# Spring2020.net
KiCad netlist of a schematic drawn in EAGLE
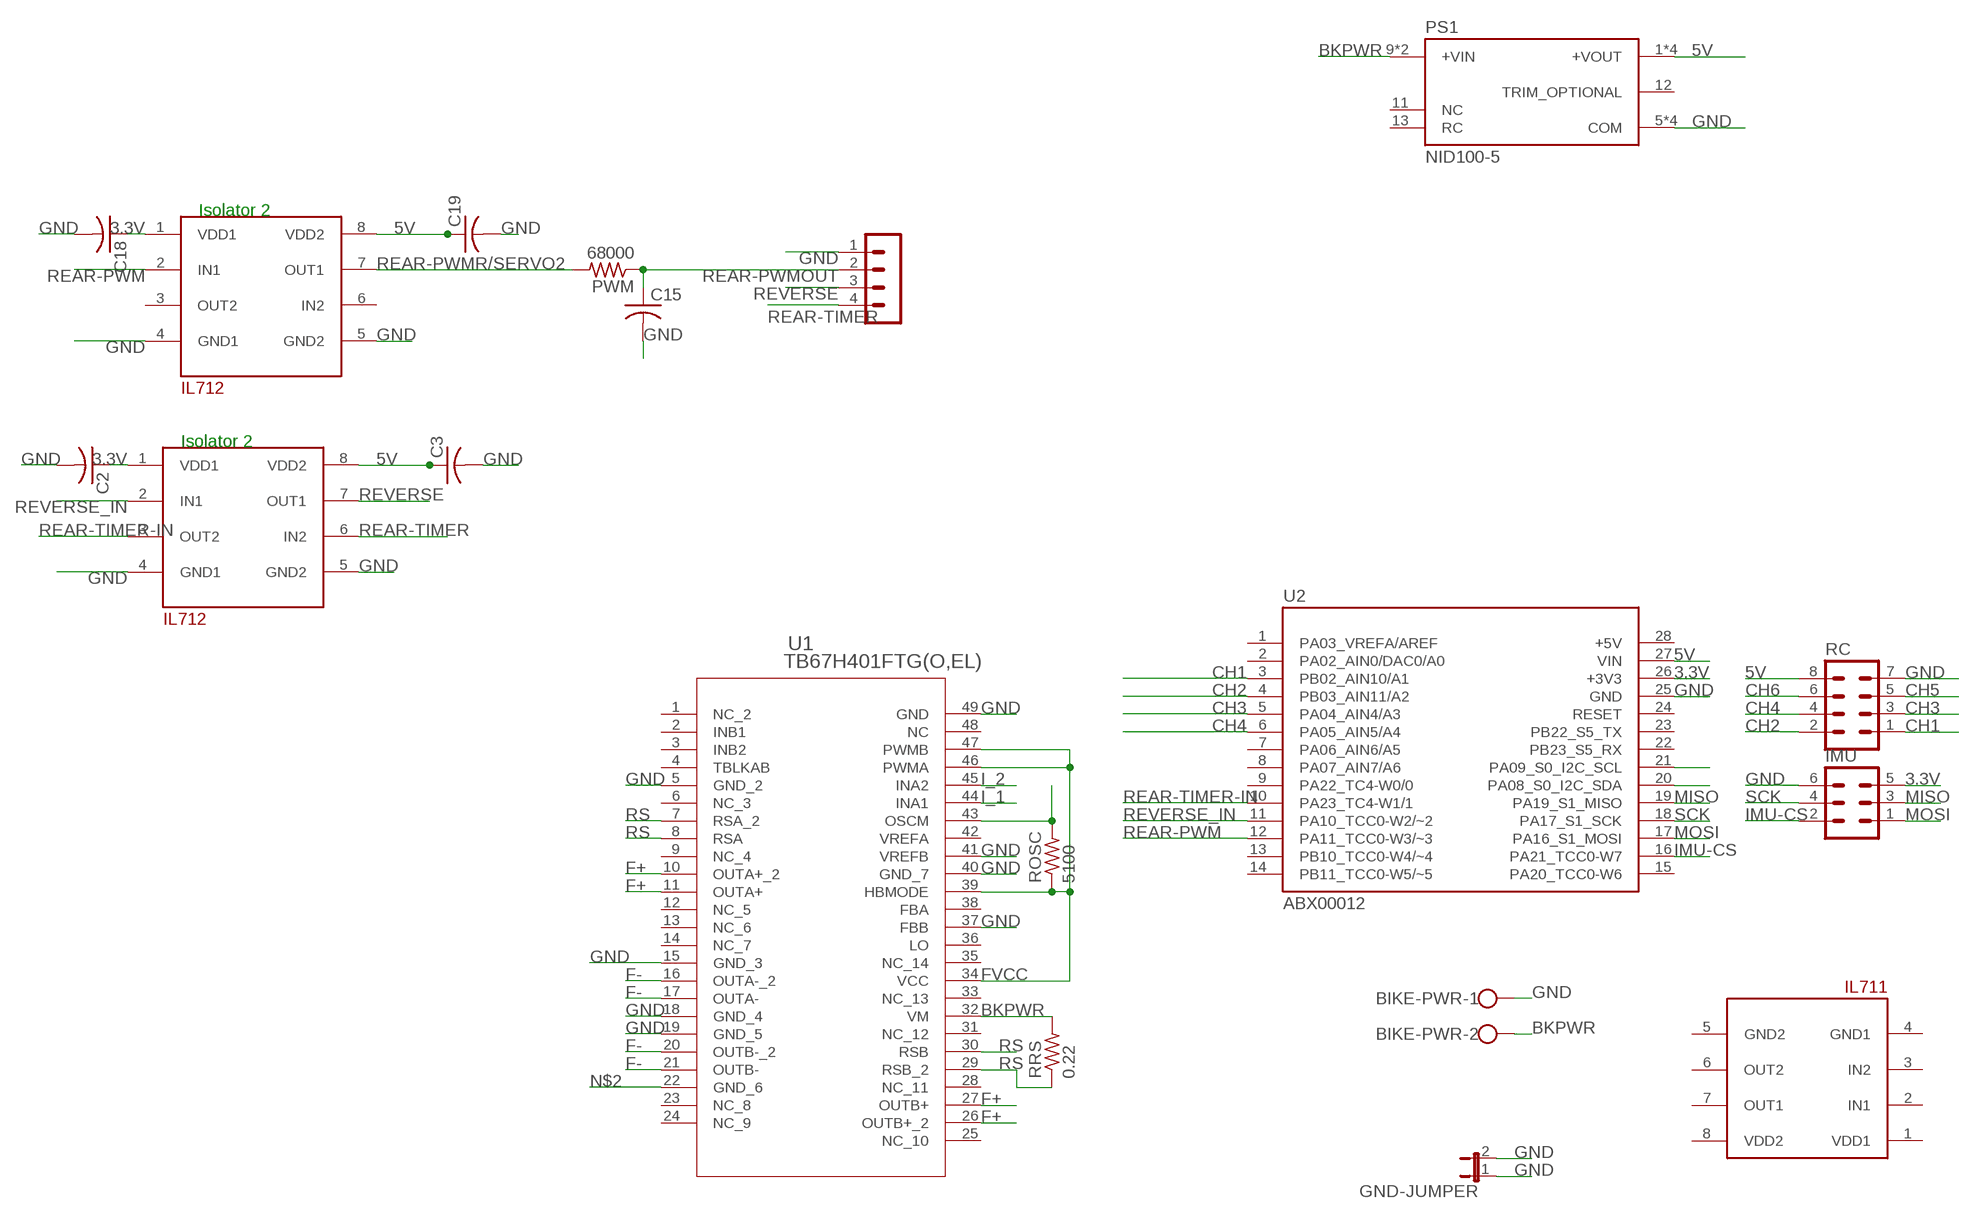
[diagram p0: schematic, sheet 1]

(export (version "E")
  (design (tool "Eeschema 10.0.6"))
  (components
    (comp (ref "BIKE-PWR")
      (value "W237-102")
      (footprint "eagle-import:W237-102")
      (fields (field (name "MPN") "237-102"))
      (libsource (lib "eagle-import") (part "W237-102"))
    )
    (comp (ref "C2")
      (value "C-US025-050X050")
      (footprint "eagle-import:C025-050X050")
      (libsource (lib "eagle-import") (part "C-US025-050X050"))
    )
    (comp (ref "C3")
      (value "C-US025-050X050")
      (footprint "eagle-import:C025-050X050")
      (libsource (lib "eagle-import") (part "C-US025-050X050"))
    )
    (comp (ref "C15")
      (value "C-US025-050X050")
      (footprint "eagle-import:C025-050X050")
      (libsource (lib "eagle-import") (part "C-US025-050X050"))
    )
    (comp (ref "C18")
      (value "C-US025-050X050")
      (footprint "eagle-import:C025-050X050")
      (libsource (lib "eagle-import") (part "C-US025-050X050"))
    )
    (comp (ref "C19")
      (value "C-US025-050X050")
      (footprint "eagle-import:C025-050X050")
      (libsource (lib "eagle-import") (part "C-US025-050X050"))
    )
    (comp (ref "GND-JUMPER")
      (value "JP1E")
      (footprint "eagle-import:JP1")
      (libsource (lib "eagle-import") (part "JP1E"))
    )
    (comp (ref "IMU")
      (value "MA03-2")
      (footprint "eagle-import:MA03-2")
      (libsource (lib "eagle-import") (part "MA03-2"))
    )
    (comp (ref "PS1")
      (value "NID100-5")
      (footprint "eagle-import:CONV_NID100-5")
      (fields (field (name "MANUFACTURER") "Meanwell"))
      (libsource (lib "eagle-import") (part "NID100-5"))
    )
    (comp (ref "PWM")
      (value "68000")
      (footprint "eagle-import:0204V")
      (libsource (lib "eagle-import") (part "R-US_0204/2V"))
    )
    (comp (ref "RC")
      (value "MA04-2")
      (footprint "eagle-import:MA04-2")
      (libsource (lib "eagle-import") (part "MA04-2"))
    )
    (comp (ref "REAR-MOTOR")
      (value "MA04-1")
      (footprint "eagle-import:MA04-1")
      (libsource (lib "eagle-import") (part "MA04-1"))
    )
    (comp (ref "ROSC")
      (value "5100")
      (footprint "eagle-import:0204V")
      (libsource (lib "eagle-import") (part "R-US_0204/2V"))
    )
    (comp (ref "RRS")
      (value "0.22")
      (footprint "eagle-import:0204V")
      (libsource (lib "eagle-import") (part "R-US_0204/2V"))
    )
    (comp (ref "U$2")
      (value "IL-712")
      (footprint "eagle-import:8PINSOIC")
      (libsource (lib "eagle-import") (part "IL-712"))
    )
    (comp (ref "U$3")
      (value "IL-711")
      (footprint "eagle-import:8PINSOIC")
      (libsource (lib "eagle-import") (part "IL-711"))
    )
    (comp (ref "U$7")
      (value "IL-712")
      (footprint "eagle-import:8PINSOIC")
      (libsource (lib "eagle-import") (part "IL-712"))
    )
    (comp (ref "U1")
      (value "TB67H401FTG(O,EL)")
      (footprint "eagle-import:P-VQFN48-0707-0P50-004_TOS")
      (fields (field (name "COPYRIGHT") "Copyright (C) 2022 Ultra Librarian. All rights reserved."))
      (libsource (lib "eagle-import") (part "TB67H401FTG(O,EL)"))
    )
    (comp (ref "U2")
      (value "ABX00012")
      (footprint "eagle-import:ARDUINO_ABX00012")
      (fields (field (name "MANUFACTURER") "Arduino"))
      (libsource (lib "eagle-import") (part "ABX00012"))
    )
  )
  (nets
    (net (code "1") (name "/+5V") (class "Default")
      (node (ref "U2") (pin "28") (pinfunction "+5V_28") (pintype "power_in"))
    )
    (net (code "2") (name "/3.3V") (class "Default")
      (node (ref "C18") (pin "1") (pinfunction "1_1") (pintype "passive"))
      (node (ref "C2") (pin "1") (pinfunction "1_1") (pintype "passive"))
      (node (ref "IMU") (pin "5") (pinfunction "5_5") (pintype "passive"))
      (node (ref "U$2") (pin "1") (pinfunction "VDD1_1") (pintype "power_in"))
      (node (ref "U$7") (pin "1") (pinfunction "VDD1_1") (pintype "power_in"))
      (node (ref "U2") (pin "26") (pinfunction "+3V3_26") (pintype "power_in"))
    )
    (net (code "3") (name "/5V") (class "Default")
      (node (ref "C19") (pin "1") (pinfunction "1_1") (pintype "passive"))
      (node (ref "C3") (pin "1") (pinfunction "1_1") (pintype "passive"))
      (node (ref "PS1") (pin "1") (pinfunction "+VOUT_1") (pintype "output"))
      (node (ref "PS1") (pin "2") (pinfunction "+VOUT_2") (pintype "output"))
      (node (ref "PS1") (pin "3") (pinfunction "+VOUT_3") (pintype "output"))
      (node (ref "PS1") (pin "4") (pinfunction "+VOUT_4") (pintype "output"))
      (node (ref "RC") (pin "8") (pinfunction "8_8") (pintype "passive"))
      (node (ref "U$2") (pin "8") (pinfunction "VDD2_8") (pintype "power_in"))
      (node (ref "U$7") (pin "8") (pinfunction "VDD2_8") (pintype "power_in"))
      (node (ref "U2") (pin "27") (pinfunction "VIN_27") (pintype "power_in"))
    )
    (net (code "4") (name "/BKPWR") (class "Default")
      (node (ref "BIKE-PWR") (pin "2") (pinfunction "KL_2") (pintype "passive"))
      (node (ref "PS1") (pin "10") (pinfunction "+VIN_10") (pintype "input"))
      (node (ref "PS1") (pin "9") (pinfunction "+VIN_9") (pintype "input"))
      (node (ref "RRS") (pin "2") (pinfunction "2_2") (pintype "passive"))
      (node (ref "U1") (pin "32") (pinfunction "VM_32") (pintype "passive"))
    )
    (net (code "5") (name "/CH1") (class "Default")
      (node (ref "RC") (pin "1") (pinfunction "1_1") (pintype "passive"))
      (node (ref "U2") (pin "3") (pinfunction "PB02_AIN10/A1_3") (pintype "bidirectional"))
    )
    (net (code "6") (name "/CH2") (class "Default")
      (node (ref "RC") (pin "2") (pinfunction "2_2") (pintype "passive"))
      (node (ref "U2") (pin "4") (pinfunction "PB03_AIN11/A2_4") (pintype "bidirectional"))
    )
    (net (code "7") (name "/CH3") (class "Default")
      (node (ref "RC") (pin "3") (pinfunction "3_3") (pintype "passive"))
      (node (ref "U2") (pin "5") (pinfunction "PA04_AIN4/A3_5") (pintype "bidirectional"))
    )
    (net (code "8") (name "/CH4") (class "Default")
      (node (ref "RC") (pin "4") (pinfunction "4_4") (pintype "passive"))
      (node (ref "U2") (pin "6") (pinfunction "PA05_AIN5/A4_6") (pintype "bidirectional"))
    )
    (net (code "9") (name "/CH5") (class "Default")
      (node (ref "RC") (pin "5") (pinfunction "5_5") (pintype "passive"))
    )
    (net (code "10") (name "/CH6") (class "Default")
      (node (ref "RC") (pin "6") (pinfunction "6_6") (pintype "passive"))
    )
    (net (code "11") (name "/F+") (class "Default")
      (node (ref "U1") (pin "10") (pinfunction "OUTA+_2_10") (pintype "output"))
      (node (ref "U1") (pin "11") (pinfunction "OUTA+_11") (pintype "output"))
      (node (ref "U1") (pin "26") (pinfunction "OUTB+_2_26") (pintype "output"))
      (node (ref "U1") (pin "27") (pinfunction "OUTB+_27") (pintype "output"))
    )
    (net (code "12") (name "/F-") (class "Default")
      (node (ref "U1") (pin "16") (pinfunction "OUTA-_2_16") (pintype "output"))
      (node (ref "U1") (pin "17") (pinfunction "OUTA-_17") (pintype "output"))
      (node (ref "U1") (pin "20") (pinfunction "OUTB-_2_20") (pintype "output"))
      (node (ref "U1") (pin "21") (pinfunction "OUTB-_21") (pintype "output"))
    )
    (net (code "13") (name "/FVCC") (class "Default")
      (node (ref "ROSC") (pin "1") (pinfunction "1_1") (pintype "passive"))
      (node (ref "U1") (pin "34") (pinfunction "VCC_34") (pintype "power_in"))
      (node (ref "U1") (pin "39") (pinfunction "HBMODE_39") (pintype "passive"))
      (node (ref "U1") (pin "46") (pinfunction "PWMA_46") (pintype "passive"))
      (node (ref "U1") (pin "47") (pinfunction "PWMB_47") (pintype "passive"))
    )
    (net (code "14") (name "/GND") (class "Default")
      (node (ref "BIKE-PWR") (pin "1") (pinfunction "KL_1") (pintype "passive"))
      (node (ref "C15") (pin "2") (pinfunction "2_2") (pintype "passive"))
      (node (ref "C18") (pin "2") (pinfunction "2_2") (pintype "passive"))
      (node (ref "C19") (pin "2") (pinfunction "2_2") (pintype "passive"))
      (node (ref "C2") (pin "2") (pinfunction "2_2") (pintype "passive"))
      (node (ref "C3") (pin "2") (pinfunction "2_2") (pintype "passive"))
      (node (ref "GND-JUMPER") (pin "1") (pinfunction "1_1") (pintype "passive"))
      (node (ref "GND-JUMPER") (pin "2") (pinfunction "2_2") (pintype "passive"))
      (node (ref "IMU") (pin "6") (pinfunction "6_6") (pintype "passive"))
      (node (ref "PS1") (pin "5") (pinfunction "COM_5") (pintype "passive"))
      (node (ref "PS1") (pin "6") (pinfunction "COM_6") (pintype "passive"))
      (node (ref "PS1") (pin "7") (pinfunction "COM_7") (pintype "passive"))
      (node (ref "PS1") (pin "8") (pinfunction "COM_8") (pintype "passive"))
      (node (ref "RC") (pin "7") (pinfunction "7_7") (pintype "passive"))
      (node (ref "REAR-MOTOR") (pin "1") (pinfunction "1_1") (pintype "passive"))
      (node (ref "U$2") (pin "4") (pinfunction "GND1_4") (pintype "power_in"))
      (node (ref "U$2") (pin "5") (pinfunction "GND2_5") (pintype "power_in"))
      (node (ref "U$7") (pin "4") (pinfunction "GND1_4") (pintype "power_in"))
      (node (ref "U$7") (pin "5") (pinfunction "GND2_5") (pintype "power_in"))
      (node (ref "U1") (pin "15") (pinfunction "GND_3_15") (pintype "passive"))
      (node (ref "U1") (pin "18") (pinfunction "GND_4_18") (pintype "passive"))
      (node (ref "U1") (pin "19") (pinfunction "GND_5_19") (pintype "passive"))
      (node (ref "U1") (pin "37") (pinfunction "FBB_37") (pintype "passive"))
      (node (ref "U1") (pin "40") (pinfunction "GND_7_40") (pintype "passive"))
      (node (ref "U1") (pin "41") (pinfunction "VREFB_41") (pintype "power_in"))
      (node (ref "U1") (pin "49") (pinfunction "GND_49") (pintype "passive"))
      (node (ref "U1") (pin "5") (pinfunction "GND_2_5") (pintype "passive"))
      (node (ref "U2") (pin "25") (pinfunction "GND_25") (pintype "power_in"))
    )
    (net (code "15") (name "/GND1") (class "Default")
      (node (ref "U$3") (pin "4") (pinfunction "GND1_4") (pintype "power_in"))
    )
    (net (code "16") (name "/GND2") (class "Default")
      (node (ref "U$3") (pin "5") (pinfunction "GND2_5") (pintype "power_in"))
    )
    (net (code "17") (name "/IMU-CS") (class "Default")
      (node (ref "IMU") (pin "2") (pinfunction "2_2") (pintype "passive"))
      (node (ref "U2") (pin "16") (pinfunction "PA21_TCC0-W7_16") (pintype "bidirectional"))
    )
    (net (code "18") (name "/I_1") (class "Default")
      (node (ref "U1") (pin "44") (pinfunction "INA1_44") (pintype "input"))
    )
    (net (code "19") (name "/I_2") (class "Default")
      (node (ref "U1") (pin "45") (pinfunction "INA2_45") (pintype "input"))
    )
    (net (code "20") (name "/MISO") (class "Default")
      (node (ref "IMU") (pin "3") (pinfunction "3_3") (pintype "passive"))
      (node (ref "U2") (pin "19") (pinfunction "PA19_S1_MISO_19") (pintype "bidirectional"))
    )
    (net (code "21") (name "/MOSI") (class "Default")
      (node (ref "IMU") (pin "1") (pinfunction "1_1") (pintype "passive"))
      (node (ref "U2") (pin "17") (pinfunction "PA16_S1_MOSI_17") (pintype "bidirectional"))
    )
    (net (code "22") (name "/N$2") (class "Default")
      (node (ref "U1") (pin "22") (pinfunction "GND_6_22") (pintype "passive"))
    )
    (net (code "23") (name "/REAR-PWM") (class "Default")
      (node (ref "U$7") (pin "2") (pinfunction "IN1_2") (pintype "input"))
      (node (ref "U2") (pin "12") (pinfunction "PA11_TCC0-W3/~{3}_12") (pintype "bidirectional"))
    )
    (net (code "24") (name "/REAR-PWMOUT") (class "Default")
      (node (ref "C15") (pin "1") (pinfunction "1_1") (pintype "passive"))
      (node (ref "PWM") (pin "1") (pinfunction "1_1") (pintype "passive"))
      (node (ref "REAR-MOTOR") (pin "2") (pinfunction "2_2") (pintype "passive"))
    )
    (net (code "25") (name "/REAR-PWMR{slash}SERVO2") (class "Default")
      (node (ref "PWM") (pin "2") (pinfunction "2_2") (pintype "passive"))
      (node (ref "U$7") (pin "7") (pinfunction "OUT1_7") (pintype "output"))
    )
    (net (code "26") (name "/REAR-TIMER") (class "Default")
      (node (ref "REAR-MOTOR") (pin "4") (pinfunction "4_4") (pintype "passive"))
      (node (ref "U$2") (pin "6") (pinfunction "IN2_6") (pintype "input"))
    )
    (net (code "27") (name "/REAR-TIMER-IN") (class "Default")
      (node (ref "U$2") (pin "3") (pinfunction "OUT2_3") (pintype "output"))
      (node (ref "U2") (pin "10") (pinfunction "PA23_TC4-W1/1_10") (pintype "bidirectional"))
    )
    (net (code "28") (name "/REVERSE") (class "Default")
      (node (ref "REAR-MOTOR") (pin "3") (pinfunction "3_3") (pintype "passive"))
      (node (ref "U$2") (pin "7") (pinfunction "OUT1_7") (pintype "output"))
    )
    (net (code "29") (name "/REVERSE_IN") (class "Default")
      (node (ref "U$2") (pin "2") (pinfunction "IN1_2") (pintype "input"))
      (node (ref "U2") (pin "11") (pinfunction "PA10_TCC0-W2/~{2}_11") (pintype "bidirectional"))
    )
    (net (code "30") (name "/RS") (class "Default")
      (node (ref "RRS") (pin "1") (pinfunction "1_1") (pintype "passive"))
      (node (ref "U1") (pin "29") (pinfunction "RSB_2_29") (pintype "passive"))
      (node (ref "U1") (pin "30") (pinfunction "RSB_30") (pintype "passive"))
      (node (ref "U1") (pin "7") (pinfunction "RSA_2_7") (pintype "passive"))
      (node (ref "U1") (pin "8") (pinfunction "RSA_8") (pintype "passive"))
    )
    (net (code "31") (name "/SCK") (class "Default")
      (node (ref "IMU") (pin "4") (pinfunction "4_4") (pintype "passive"))
      (node (ref "U2") (pin "18") (pinfunction "PA17_S1_SCK_18") (pintype "bidirectional"))
    )
    (net (code "32") (name "/VDD1") (class "Default")
      (node (ref "U$3") (pin "1") (pinfunction "VDD1_1") (pintype "power_in"))
    )
    (net (code "33") (name "/VDD2") (class "Default")
      (node (ref "U$3") (pin "8") (pinfunction "VDD2_8") (pintype "power_in"))
    )
    (net (code "34") (name "/VREFA") (class "Default")
      (node (ref "U1") (pin "42") (pinfunction "VREFA_42") (pintype "power_in"))
    )
    (net (code "35") (name "Net-(U1-OSCM)") (class "Default")
      (node (ref "ROSC") (pin "2") (pinfunction "2_2") (pintype "passive"))
      (node (ref "U1") (pin "43") (pinfunction "OSCM_43") (pintype "passive"))
    )
    (net (code "36") (name "unconnected-(PS1-NC-Pad11)") (class "Default")
      (node (ref "PS1") (pin "11") (pinfunction "NC_11") (pintype "no_connect"))
    )
    (net (code "37") (name "unconnected-(PS1-RC-Pad13)") (class "Default")
      (node (ref "PS1") (pin "13") (pinfunction "RC_13") (pintype "passive"))
    )
    (net (code "38") (name "unconnected-(PS1-TRIM_OPTIONAL-Pad12)") (class "Default")
      (node (ref "PS1") (pin "12") (pinfunction "TRIM_OPTIONAL_12") (pintype "passive"))
    )
    (net (code "39") (name "unconnected-(U$3-IN1-Pad2)") (class "Default")
      (node (ref "U$3") (pin "2") (pinfunction "IN1_2") (pintype "input"))
    )
    (net (code "40") (name "unconnected-(U$3-IN2-Pad3)") (class "Default")
      (node (ref "U$3") (pin "3") (pinfunction "IN2_3") (pintype "input"))
    )
    (net (code "41") (name "unconnected-(U$3-OUT1-Pad7)") (class "Default")
      (node (ref "U$3") (pin "7") (pinfunction "OUT1_7") (pintype "output"))
    )
    (net (code "42") (name "unconnected-(U$3-OUT2-Pad6)") (class "Default")
      (node (ref "U$3") (pin "6") (pinfunction "OUT2_6") (pintype "output"))
    )
    (net (code "43") (name "unconnected-(U$7-IN2-Pad6)") (class "Default")
      (node (ref "U$7") (pin "6") (pinfunction "IN2_6") (pintype "input"))
    )
    (net (code "44") (name "unconnected-(U$7-OUT2-Pad3)") (class "Default")
      (node (ref "U$7") (pin "3") (pinfunction "OUT2_3") (pintype "output"))
    )
    (net (code "45") (name "unconnected-(U1-FBA-Pad38)") (class "Default")
      (node (ref "U1") (pin "38") (pinfunction "FBA_38") (pintype "passive"))
    )
    (net (code "46") (name "unconnected-(U1-INB1-Pad2)") (class "Default")
      (node (ref "U1") (pin "2") (pinfunction "INB1_2") (pintype "input"))
    )
    (net (code "47") (name "unconnected-(U1-INB2-Pad3)") (class "Default")
      (node (ref "U1") (pin "3") (pinfunction "INB2_3") (pintype "input"))
    )
    (net (code "48") (name "unconnected-(U1-LO-Pad36)") (class "Default")
      (node (ref "U1") (pin "36") (pinfunction "LO_36") (pintype "passive"))
    )
    (net (code "49") (name "unconnected-(U1-NC-Pad48)") (class "Default")
      (node (ref "U1") (pin "48") (pinfunction "NC_48") (pintype "no_connect"))
    )
    (net (code "50") (name "unconnected-(U1-NC_2-Pad1)") (class "Default")
      (node (ref "U1") (pin "1") (pinfunction "NC_2_1") (pintype "no_connect"))
    )
    (net (code "51") (name "unconnected-(U1-NC_3-Pad6)") (class "Default")
      (node (ref "U1") (pin "6") (pinfunction "NC_3_6") (pintype "no_connect"))
    )
    (net (code "52") (name "unconnected-(U1-NC_4-Pad9)") (class "Default")
      (node (ref "U1") (pin "9") (pinfunction "NC_4_9") (pintype "no_connect"))
    )
    (net (code "53") (name "unconnected-(U1-NC_5-Pad12)") (class "Default")
      (node (ref "U1") (pin "12") (pinfunction "NC_5_12") (pintype "no_connect"))
    )
    (net (code "54") (name "unconnected-(U1-NC_6-Pad13)") (class "Default")
      (node (ref "U1") (pin "13") (pinfunction "NC_6_13") (pintype "no_connect"))
    )
    (net (code "55") (name "unconnected-(U1-NC_7-Pad14)") (class "Default")
      (node (ref "U1") (pin "14") (pinfunction "NC_7_14") (pintype "no_connect"))
    )
    (net (code "56") (name "unconnected-(U1-NC_8-Pad23)") (class "Default")
      (node (ref "U1") (pin "23") (pinfunction "NC_8_23") (pintype "no_connect"))
    )
    (net (code "57") (name "unconnected-(U1-NC_9-Pad24)") (class "Default")
      (node (ref "U1") (pin "24") (pinfunction "NC_9_24") (pintype "no_connect"))
    )
    (net (code "58") (name "unconnected-(U1-NC_10-Pad25)") (class "Default")
      (node (ref "U1") (pin "25") (pinfunction "NC_10_25") (pintype "no_connect"))
    )
    (net (code "59") (name "unconnected-(U1-NC_11-Pad28)") (class "Default")
      (node (ref "U1") (pin "28") (pinfunction "NC_11_28") (pintype "no_connect"))
    )
    (net (code "60") (name "unconnected-(U1-NC_12-Pad31)") (class "Default")
      (node (ref "U1") (pin "31") (pinfunction "NC_12_31") (pintype "no_connect"))
    )
    (net (code "61") (name "unconnected-(U1-NC_13-Pad33)") (class "Default")
      (node (ref "U1") (pin "33") (pinfunction "NC_13_33") (pintype "no_connect"))
    )
    (net (code "62") (name "unconnected-(U1-NC_14-Pad35)") (class "Default")
      (node (ref "U1") (pin "35") (pinfunction "NC_14_35") (pintype "no_connect"))
    )
    (net (code "63") (name "unconnected-(U1-TBLKAB-Pad4)") (class "Default")
      (node (ref "U1") (pin "4") (pinfunction "TBLKAB_4") (pintype "passive"))
    )
    (net (code "64") (name "unconnected-(U2-PA02_AIN0{slash}DAC0{slash}A0-Pad2)") (class "Default")
      (node (ref "U2") (pin "2") (pinfunction "PA02_AIN0/DAC0/A0_2") (pintype "bidirectional"))
    )
    (net (code "65") (name "unconnected-(U2-PA03_VREFA{slash}AREF-Pad1)") (class "Default")
      (node (ref "U2") (pin "1") (pinfunction "PA03_VREFA/AREF_1") (pintype "bidirectional"))
    )
    (net (code "66") (name "unconnected-(U2-PA06_AIN6{slash}A5-Pad7)") (class "Default")
      (node (ref "U2") (pin "7") (pinfunction "PA06_AIN6/A5_7") (pintype "bidirectional"))
    )
    (net (code "67") (name "unconnected-(U2-PA07_AIN7{slash}A6-Pad8)") (class "Default")
      (node (ref "U2") (pin "8") (pinfunction "PA07_AIN7/A6_8") (pintype "bidirectional"))
    )
    (net (code "68") (name "unconnected-(U2-PA08_S0_I2C_SDA-Pad20)") (class "Default")
      (node (ref "U2") (pin "20") (pinfunction "PA08_S0_I2C_SDA_20") (pintype "bidirectional"))
    )
    (net (code "69") (name "unconnected-(U2-PA09_S0_I2C_SCL-Pad21)") (class "Default")
      (node (ref "U2") (pin "21") (pinfunction "PA09_S0_I2C_SCL_21") (pintype "bidirectional"))
    )
    (net (code "70") (name "unconnected-(U2-PA20_TCC0-W6-Pad15)") (class "Default")
      (node (ref "U2") (pin "15") (pinfunction "PA20_TCC0-W6_15") (pintype "bidirectional"))
    )
    (net (code "71") (name "unconnected-(U2-PA22_TC4-W0{slash}0-Pad9)") (class "Default")
      (node (ref "U2") (pin "9") (pinfunction "PA22_TC4-W0/0_9") (pintype "bidirectional"))
    )
    (net (code "72") (name "unconnected-(U2-PB10_TCC0-W4{slash}~{4}-Pad13)") (class "Default")
      (node (ref "U2") (pin "13") (pinfunction "PB10_TCC0-W4/~{4}_13") (pintype "bidirectional"))
    )
    (net (code "73") (name "unconnected-(U2-PB11_TCC0-W5{slash}~{5}-Pad14)") (class "Default")
      (node (ref "U2") (pin "14") (pinfunction "PB11_TCC0-W5/~{5}_14") (pintype "bidirectional"))
    )
    (net (code "74") (name "unconnected-(U2-PB22_S5_TX-Pad23)") (class "Default")
      (node (ref "U2") (pin "23") (pinfunction "PB22_S5_TX_23") (pintype "bidirectional"))
    )
    (net (code "75") (name "unconnected-(U2-PB23_S5_RX-Pad22)") (class "Default")
      (node (ref "U2") (pin "22") (pinfunction "PB23_S5_RX_22") (pintype "bidirectional"))
    )
    (net (code "76") (name "unconnected-(U2-RESET-Pad24)") (class "Default")
      (node (ref "U2") (pin "24") (pinfunction "RESET_24") (pintype "input"))
    )
  )
)
